# Carduino.net
KiCad netlist of a schematic drawn in Altium Designer
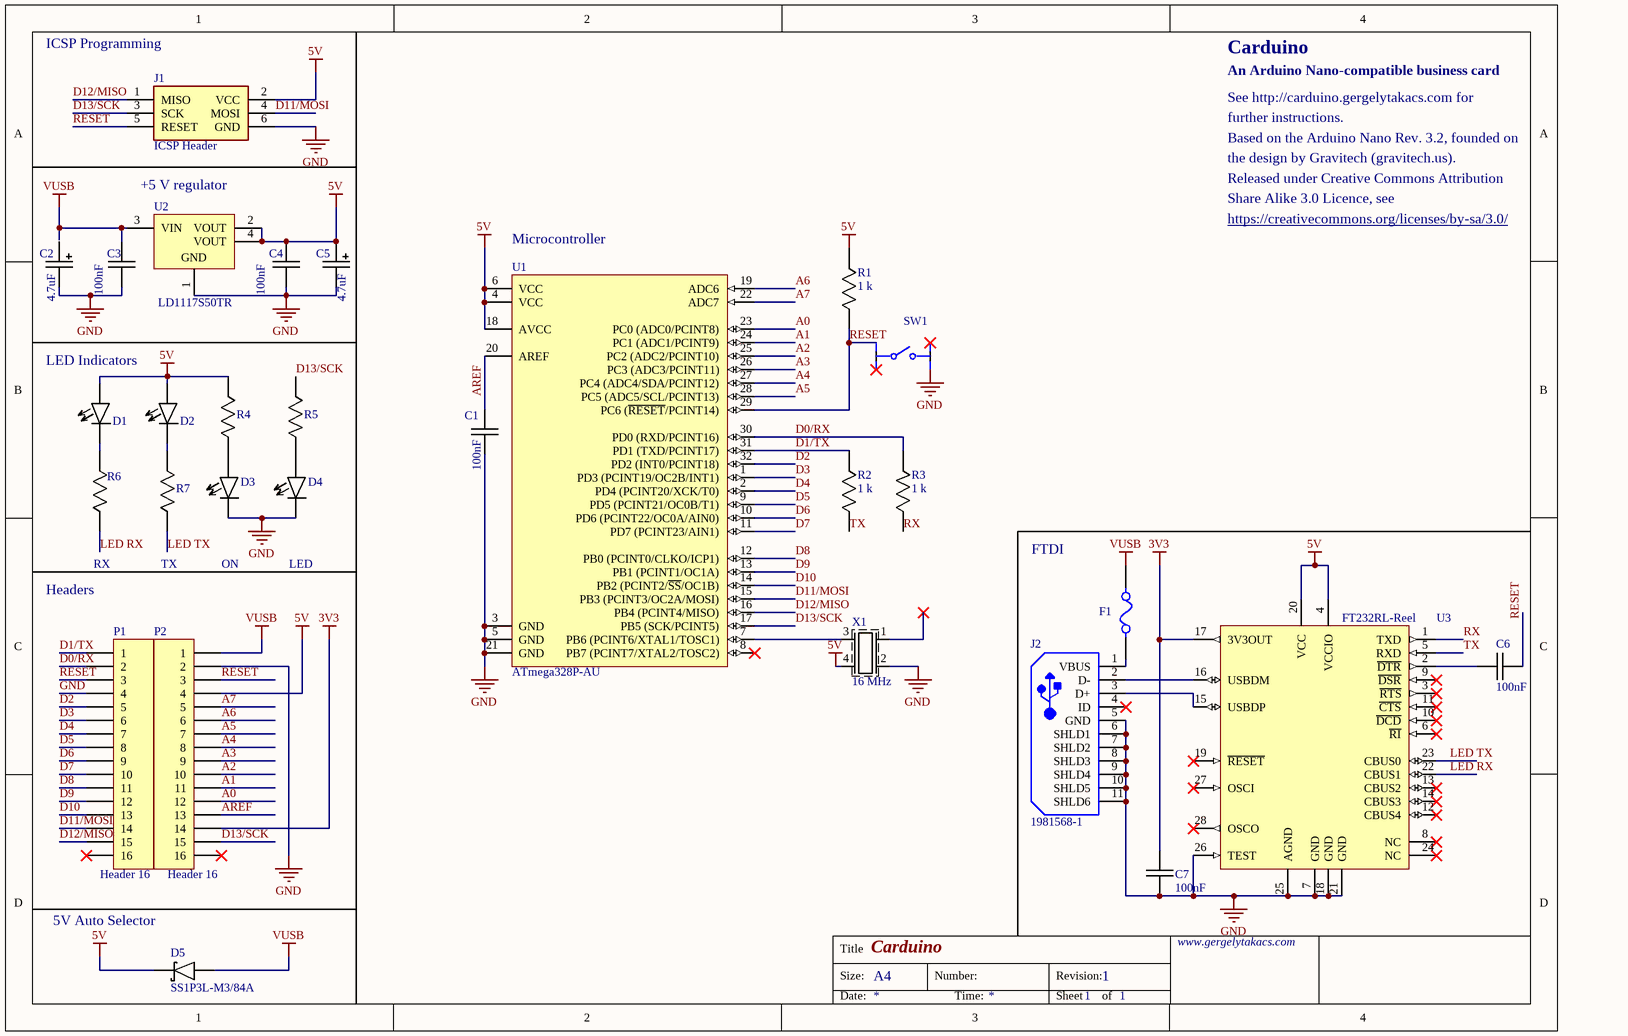
[diagram p0: Carduino.SchDoc]

(export (version "E")
  (design (tool "Eeschema 10.0.6"))
  (components
    (comp (ref "C1")
      (value "100nF")
      (footprint "CAPC2013X09N")
      (description "Ceramic condenser MLCC; 100nF; 25V; X7R; ±10%; SMD; 0805")
      (libsource (lib "Capacitors") (part "100 uF,  ceramic, 0805, Kemet"))
    )
    (comp (ref "C2")
      (value "4.7uF")
      (footprint "CAP body B")
      (description "4,7uF; 25VDC; SMD; Puzd: B; ±10%; -55÷125°C")
      (libsource (lib "Capacitors") (part "4.7uF, Tantallum"))
    )
    (comp (ref "C3")
      (value "100nF")
      (footprint "CAPC2013X09N")
      (description "Ceramic condenser MLCC; 100nF; 25V; X7R; ±10%; SMD; 0805")
      (libsource (lib "Capacitors") (part "100 uF,  ceramic, 0805, Kemet"))
    )
    (comp (ref "C4")
      (value "100nF")
      (footprint "CAPC2013X09N")
      (description "Ceramic condenser MLCC; 100nF; 25V; X7R; ±10%; SMD; 0805")
      (libsource (lib "Capacitors") (part "100 uF,  ceramic, 0805, Kemet"))
    )
    (comp (ref "C5")
      (value "4.7uF")
      (footprint "CAP body B")
      (description "4,7uF; 25VDC; SMD; Puzd: B; ±10%; -55÷125°C")
      (libsource (lib "Capacitors") (part "4.7uF, Tantallum"))
    )
    (comp (ref "C6")
      (value "100nF")
      (footprint "CAPC2013X09N")
      (description "Ceramic condenser MLCC; 100nF; 25V; X7R; ±10%; SMD; 0805")
      (libsource (lib "Capacitors") (part "100 uF,  ceramic, 0805, Kemet"))
    )
    (comp (ref "C7")
      (value "100nF")
      (footprint "CAPC2013X09N")
      (description "Ceramic condenser MLCC; 100nF; 25V; X7R; ±10%; SMD; 0805")
      (libsource (lib "Capacitors") (part "100 uF,  ceramic, 0805, Kemet"))
    )
    (comp (ref "D1")
      (value "OSXX0805C1E")
      (footprint "DIOC2012X09N")
      (description "OptoSupply Single Chip LED 0805")
      (fields
        (field (name "CREATOR") "Gergely Takacs")
        (field (name "CREATOR WWW") "http://www.gergelytakacs.com")
      )
      (libsource (lib "OptoSupplyLED") (part "OptoSupply RED"))
    )
    (comp (ref "D2")
      (value "OSXX0805C1E")
      (footprint "DIOC2012X09N")
      (description "OptoSupply Single Chip LED 0805")
      (fields
        (field (name "CREATOR") "Gergely Takacs")
        (field (name "CREATOR WWW") "http://www.gergelytakacs.com")
      )
      (libsource (lib "OptoSupplyLED") (part "OptoSupply RED"))
    )
    (comp (ref "D3")
      (value "OSXX0805C1E")
      (footprint "DIOC2012X09N")
      (description "OptoSupply Single Chip LED 0805")
      (fields
        (field (name "CREATOR") "Gergely Takacs")
        (field (name "CREATOR WWW") "http://www.gergelytakacs.com")
      )
      (libsource (lib "OptoSupplyLED") (part "OptoSupply RED"))
    )
    (comp (ref "D4")
      (value "OSXX0805C1E")
      (footprint "DIOC2012X09N")
      (description "OptoSupply Single Chip LED 0805")
      (fields
        (field (name "CREATOR") "Gergely Takacs")
        (field (name "CREATOR WWW") "http://www.gergelytakacs.com")
      )
      (libsource (lib "OptoSupplyLED") (part "OptoSupply RED"))
    )
    (comp (ref "D5")
      (value "SS1P3L-M3/84A")
      (footprint "DIOM3420X11N")
      (description "VISHAY SS1P3L-M3/84A  Dióda: usmerňovacia Schottky; SMD; 30V; 1A; DO220AA, SMP")
      (libsource (lib "Diodes") (part "SS1P3L"))
    )
    (comp (ref "F1")
      (value "ECE SR050-06")
      (footprint "RESC2113X12N")
      (description "FUSE PTC RESETTABLE .50A")
      (libsource (lib "Fuses") (part "ECE SR050-06"))
    )
    (comp (ref "J1")
      (value "Conn_3M_961206-6404-AR_eec")
      (footprint "3M_961206-6404-AR_0")
      (description "CONN HEADER VERT DUAL 6POS GOLD")
      (fields
        (field (name "MANUFACTURER") "3M")
        (field (name "MOUSER PART NUMBER") "517-9612066404AR")
        (field (name "PART NUMBER") "ICSP Header")
      )
      (libsource (lib "ICSP") (part "Conn_3M_961206-6404-AR_eec"))
    )
    (comp (ref "J2")
      (value "1981568-1")
      (footprint "TECO-1981568-5_V")
      (description "Micro USB Receptacle Standard Type B Assy, 5-Pin SMD, RoHS, Tape and Reel")
      (fields (field (name "MANUFACTURER") "TE Connectivity"))
      (libsource (lib "Connectors") (part "1981568-1"))
    )
    (comp (ref "P1")
      (value "Header 16")
      (footprint "HDR1X16")
      (description "Header, 16-Pin")
      (fields (field (name "PUBLISHER") "Altium Limited"))
      (libsource (lib "Miscellaneous Connectors") (part "Header 16"))
    )
    (comp (ref "P2")
      (value "Header 16")
      (footprint "HDR1X16")
      (description "Header, 16-Pin")
      (fields (field (name "PUBLISHER") "Altium Limited"))
      (libsource (lib "") (part "Header 16_1"))
    )
    (comp (ref "R1")
      (value "1 k")
      (footprint "RESC2112X05N")
      (description "ROYAL OHM HP05W3F1001T5E  Rezistor: thick film; vysokovýkonný; SMD; 0805; 1kΩ; 0,3W; ±1%")
      (libsource (lib "Resistors") (part "1k, 0805, Royal Ohm"))
    )
    (comp (ref "R2")
      (value "1 k")
      (footprint "RESC2112X05N")
      (description "ROYAL OHM HP05W3F1001T5E  Rezistor: thick film; vysokovýkonný; SMD; 0805; 1kΩ; 0,3W; ±1%")
      (libsource (lib "Resistors") (part "1k, 0805, Royal Ohm"))
    )
    (comp (ref "R3")
      (value "1 k")
      (footprint "RESC2112X05N")
      (description "ROYAL OHM HP05W3F1001T5E  Rezistor: thick film; vysokovýkonný; SMD; 0805; 1kΩ; 0,3W; ±1%")
      (libsource (lib "Resistors") (part "1k, 0805, Royal Ohm"))
    )
    (comp (ref "R4")
      (value "270 Ohm, 0805")
      (footprint "RESC2112X05N")
      (description "VISHAY CRCW...BC Thick Film Commodity Resistor")
      (libsource (lib "Vishay Resistors") (part "270 Ohm, 0805, Resistor"))
    )
    (comp (ref "R5")
      (value "270 Ohm, 0805")
      (footprint "RESC2112X05N")
      (description "VISHAY CRCW...BC Thick Film Commodity Resistor")
      (libsource (lib "Vishay Resistors") (part "270 Ohm, 0805, Resistor"))
    )
    (comp (ref "R6")
      (value "270 Ohm, 0805")
      (footprint "RESC2112X05N")
      (description "VISHAY CRCW...BC Thick Film Commodity Resistor")
      (libsource (lib "Vishay Resistors") (part "270 Ohm, 0805, Resistor"))
    )
    (comp (ref "R7")
      (value "270 Ohm, 0805")
      (footprint "RESC2112X05N")
      (description "VISHAY CRCW...BC Thick Film Commodity Resistor")
      (libsource (lib "Vishay Resistors") (part "270 Ohm, 0805, Resistor"))
    )
    (comp (ref "SW1")
      (value "Switch_TE_1825910-7_eec")
      (footprint "TE_1825910-7_0")
      (description "SWITCH Tactile Switch SPST-NO Top Actuated Through Hole")
      (fields (field (name "PART NUMBER") "1825910-7") (field (name "MANUFACTURER") "TE"))
      (libsource (lib "Switches") (part "Switch_TE_1825910-7_eec"))
    )
    (comp (ref "U1")
      (value "ATmega328P-AU")
      (footprint "32A_N")
      (libsource (lib "Atmel Microcontroller megaAVR") (part "ATmega328P-AU"))
    )
    (comp (ref "U2")
      (value "LD1117S50TR")
      (footprint "SOT-223_N")
      (description "Fixed Low Drop Positive Voltage Regulator, 5V, 4-Pin SOT-223, Tape and Reel")
      (libsource (lib "STMicroelectronics Power Management Linear Regulator") (part "LD1117S50TR"))
    )
    (comp (ref "U3")
      (value "FT232RL-Reel")
      (footprint "SSOP-28_N")
      (description "USB UART Asynchronous Serial Data Transfer Chip, 28-pin SSOP, Tape and Reel")
      (fields (field (name "MANUFACTURER") "FTDI"))
      (libsource (lib "FTDI FT Series") (part "FT232RL-Reel"))
    )
    (comp (ref "X1")
      (value "16 MHz")
      (footprint "DFN598P720X140-4N")
      (description "QD FREQUENCY PRODUCTS LF SPXO018034")
      (libsource (lib "Xtals") (part "16 MHz, IQD FREQUENCY PRODUCTS"))
    )
  )
  (nets
    (net (code "1") (name "/A0") (class "Default")
      (node (ref "P2") (pin "12") (pinfunction "12_12") (pintype "passive"))
      (node (ref "U1") (pin "23") (pinfunction "PC0_(ADC0/PCINT8)_23") (pintype "bidirectional"))
    )
    (net (code "2") (name "/A1") (class "Default")
      (node (ref "P2") (pin "11") (pinfunction "11_11") (pintype "passive"))
      (node (ref "U1") (pin "24") (pinfunction "PC1_(ADC1/PCINT9)_24") (pintype "bidirectional"))
    )
    (net (code "3") (name "/A2") (class "Default")
      (node (ref "P2") (pin "10") (pinfunction "10_10") (pintype "passive"))
      (node (ref "U1") (pin "25") (pinfunction "PC2_(ADC2/PCINT10)_25") (pintype "bidirectional"))
    )
    (net (code "4") (name "/A3") (class "Default")
      (node (ref "P2") (pin "9") (pinfunction "9_9") (pintype "passive"))
      (node (ref "U1") (pin "26") (pinfunction "PC3_(ADC3/PCINT11)_26") (pintype "bidirectional"))
    )
    (net (code "5") (name "/A4") (class "Default")
      (node (ref "P2") (pin "8") (pinfunction "8_8") (pintype "passive"))
      (node (ref "U1") (pin "27") (pinfunction "PC4_(ADC4/SDA/PCINT12)_27") (pintype "bidirectional"))
    )
    (net (code "6") (name "/A5") (class "Default")
      (node (ref "P2") (pin "7") (pinfunction "7_7") (pintype "passive"))
      (node (ref "U1") (pin "28") (pinfunction "PC5_(ADC5/SCL/PCINT13)_28") (pintype "bidirectional"))
    )
    (net (code "7") (name "/A6") (class "Default")
      (node (ref "P2") (pin "6") (pinfunction "6_6") (pintype "passive"))
      (node (ref "U1") (pin "19") (pinfunction "ADC6_19") (pintype "input"))
    )
    (net (code "8") (name "/A7") (class "Default")
      (node (ref "P2") (pin "5") (pinfunction "5_5") (pintype "passive"))
      (node (ref "U1") (pin "22") (pinfunction "ADC7_22") (pintype "input"))
    )
    (net (code "9") (name "/AREF") (class "Default")
      (node (ref "C1") (pin "1") (pinfunction "1_1") (pintype "passive"))
      (node (ref "P2") (pin "13") (pinfunction "13_13") (pintype "passive"))
      (node (ref "U1") (pin "20") (pinfunction "AREF_20") (pintype "passive"))
    )
    (net (code "10") (name "/D0{slash}RX") (class "Default")
      (node (ref "P1") (pin "2") (pinfunction "2_2") (pintype "passive"))
      (node (ref "R3") (pin "2") (pinfunction "2_2") (pintype "passive"))
      (node (ref "U1") (pin "30") (pinfunction "PD0_(RXD/PCINT16)_30") (pintype "bidirectional"))
    )
    (net (code "11") (name "/D1{slash}TX") (class "Default")
      (node (ref "P1") (pin "1") (pinfunction "1_1") (pintype "passive"))
      (node (ref "R2") (pin "1") (pinfunction "1_1") (pintype "passive"))
      (node (ref "U1") (pin "31") (pinfunction "PD1_(TXD/PCINT17)_31") (pintype "bidirectional"))
    )
    (net (code "12") (name "/D2") (class "Default")
      (node (ref "P1") (pin "5") (pinfunction "5_5") (pintype "passive"))
      (node (ref "U1") (pin "32") (pinfunction "PD2_(INT0/PCINT18)_32") (pintype "bidirectional"))
    )
    (net (code "13") (name "/D3") (class "Default")
      (node (ref "P1") (pin "6") (pinfunction "6_6") (pintype "passive"))
      (node (ref "U1") (pin "1") (pinfunction "PD3_(PCINT19/OC2B/INT1)_1") (pintype "bidirectional"))
    )
    (net (code "14") (name "/D4") (class "Default")
      (node (ref "P1") (pin "7") (pinfunction "7_7") (pintype "passive"))
      (node (ref "U1") (pin "2") (pinfunction "PD4_(PCINT20/XCK/T0)_2") (pintype "bidirectional"))
    )
    (net (code "15") (name "/D5") (class "Default")
      (node (ref "P1") (pin "8") (pinfunction "8_8") (pintype "passive"))
      (node (ref "U1") (pin "9") (pinfunction "PD5_(PCINT21/OC0B/T1)_9") (pintype "bidirectional"))
    )
    (net (code "16") (name "/D6") (class "Default")
      (node (ref "P1") (pin "9") (pinfunction "9_9") (pintype "passive"))
      (node (ref "U1") (pin "10") (pinfunction "PD6_(PCINT22/OC0A/AIN0)_10") (pintype "bidirectional"))
    )
    (net (code "17") (name "/D7") (class "Default")
      (node (ref "P1") (pin "10") (pinfunction "10_10") (pintype "passive"))
      (node (ref "U1") (pin "11") (pinfunction "PD7_(PCINT23/AIN1)_11") (pintype "bidirectional"))
    )
    (net (code "18") (name "/D8") (class "Default")
      (node (ref "P1") (pin "11") (pinfunction "11_11") (pintype "passive"))
      (node (ref "U1") (pin "12") (pinfunction "PB0_(PCINT0/CLKO/ICP1)_12") (pintype "bidirectional"))
    )
    (net (code "19") (name "/D9") (class "Default")
      (node (ref "P1") (pin "12") (pinfunction "12_12") (pintype "passive"))
      (node (ref "U1") (pin "13") (pinfunction "PB1_(PCINT1/OC1A)_13") (pintype "bidirectional"))
    )
    (net (code "20") (name "/D10") (class "Default")
      (node (ref "P1") (pin "13") (pinfunction "13_13") (pintype "passive"))
      (node (ref "U1") (pin "14") (pinfunction "PB2_(PCINT2/~{SS}/OC1B)_14") (pintype "bidirectional"))
    )
    (net (code "21") (name "/D11{slash}MOSI") (class "Default")
      (node (ref "J1") (pin "4") (pinfunction "MOSI_4") (pintype "passive"))
      (node (ref "P1") (pin "14") (pinfunction "14_14") (pintype "passive"))
      (node (ref "U1") (pin "15") (pinfunction "PB3_(PCINT3/OC2A/MOSI)_15") (pintype "bidirectional"))
    )
    (net (code "22") (name "/D12{slash}MISO") (class "Default")
      (node (ref "J1") (pin "1") (pinfunction "MISO_1") (pintype "passive"))
      (node (ref "P1") (pin "15") (pinfunction "15_15") (pintype "passive"))
      (node (ref "U1") (pin "16") (pinfunction "PB4_(PCINT4/MISO)_16") (pintype "bidirectional"))
    )
    (net (code "23") (name "/D13{slash}SCK") (class "Default")
      (node (ref "J1") (pin "3") (pinfunction "SCK_3") (pintype "passive"))
      (node (ref "P2") (pin "15") (pinfunction "15_15") (pintype "passive"))
      (node (ref "R5") (pin "1") (pinfunction "1_1") (pintype "passive"))
      (node (ref "U1") (pin "17") (pinfunction "PB5_(SCK/PCINT5)_17") (pintype "bidirectional"))
    )
    (net (code "24") (name "/LED RX") (class "Default")
      (node (ref "R6") (pin "2") (pinfunction "2_2") (pintype "passive"))
      (node (ref "U3") (pin "22") (pinfunction "CBUS1_22") (pintype "bidirectional"))
    )
    (net (code "25") (name "/LED TX") (class "Default")
      (node (ref "R7") (pin "2") (pinfunction "2_2") (pintype "passive"))
      (node (ref "U3") (pin "23") (pinfunction "CBUS0_23") (pintype "bidirectional"))
    )
    (net (code "26") (name "/RESET") (class "Default")
      (node (ref "C6") (pin "2") (pinfunction "2_2") (pintype "passive"))
      (node (ref "J1") (pin "5") (pinfunction "RESET_5") (pintype "passive"))
      (node (ref "P1") (pin "3") (pinfunction "3_3") (pintype "passive"))
      (node (ref "P2") (pin "3") (pinfunction "3_3") (pintype "passive"))
      (node (ref "R1") (pin "2") (pinfunction "2_2") (pintype "passive"))
      (node (ref "SW1") (pin "1") (pinfunction "1_1") (pintype "passive"))
      (node (ref "U1") (pin "29") (pinfunction "PC6_(~{RESET}/PCINT14)_29") (pintype "bidirectional"))
    )
    (net (code "27") (name "/RX") (class "Default")
      (node (ref "R3") (pin "1") (pinfunction "1_1") (pintype "passive"))
      (node (ref "U3") (pin "1") (pinfunction "TXD_1") (pintype "output"))
    )
    (net (code "28") (name "/TX") (class "Default")
      (node (ref "R2") (pin "2") (pinfunction "2_2") (pintype "passive"))
      (node (ref "U3") (pin "5") (pinfunction "RXD_5") (pintype "input"))
    )
    (net (code "29") (name "3V3") (class "Default")
      (node (ref "C7") (pin "2") (pinfunction "2_2") (pintype "passive"))
      (node (ref "P2") (pin "14") (pinfunction "14_14") (pintype "passive"))
      (node (ref "U3") (pin "17") (pinfunction "3V3OUT_17") (pintype "output"))
    )
    (net (code "30") (name "5V") (class "Default")
      (node (ref "C4") (pin "1") (pinfunction "1_1") (pintype "passive"))
      (node (ref "C5") (pin "1") (pinfunction "1_1") (pintype "passive"))
      (node (ref "D1") (pin "2") (pinfunction "2_2") (pintype "passive"))
      (node (ref "D2") (pin "2") (pinfunction "2_2") (pintype "passive"))
      (node (ref "D5") (pin "1") (pinfunction "1_1") (pintype "passive"))
      (node (ref "J1") (pin "2") (pinfunction "VCC_2") (pintype "passive"))
      (node (ref "P2") (pin "4") (pinfunction "4_4") (pintype "passive"))
      (node (ref "R1") (pin "1") (pinfunction "1_1") (pintype "passive"))
      (node (ref "R4") (pin "1") (pinfunction "1_1") (pintype "passive"))
      (node (ref "U1") (pin "18") (pinfunction "AVCC_18") (pintype "power_in"))
      (node (ref "U1") (pin "4") (pinfunction "VCC_4") (pintype "power_in"))
      (node (ref "U1") (pin "6") (pinfunction "VCC_6") (pintype "power_in"))
      (node (ref "U2") (pin "2") (pinfunction "VOUT_2") (pintype "power_in"))
      (node (ref "U2") (pin "4") (pinfunction "VOUT_4") (pintype "power_in"))
      (node (ref "U3") (pin "20") (pinfunction "VCC_20") (pintype "power_in"))
      (node (ref "U3") (pin "4") (pinfunction "VCCIO_4") (pintype "power_in"))
      (node (ref "X1") (pin "4") (pinfunction "4_4") (pintype "passive"))
    )
    (net (code "31") (name "GND") (class "Default")
      (node (ref "C1") (pin "2") (pinfunction "2_2") (pintype "passive"))
      (node (ref "C2") (pin "2") (pinfunction "2_2") (pintype "passive"))
      (node (ref "C3") (pin "1") (pinfunction "1_1") (pintype "passive"))
      (node (ref "C4") (pin "2") (pinfunction "2_2") (pintype "passive"))
      (node (ref "C5") (pin "2") (pinfunction "2_2") (pintype "passive"))
      (node (ref "C7") (pin "1") (pinfunction "1_1") (pintype "passive"))
      (node (ref "D3") (pin "1") (pinfunction "1_1") (pintype "passive"))
      (node (ref "D4") (pin "1") (pinfunction "1_1") (pintype "passive"))
      (node (ref "J1") (pin "6") (pinfunction "GND_6") (pintype "passive"))
      (node (ref "J2") (pin "10") (pinfunction "SHLD5_10") (pintype "passive"))
      (node (ref "J2") (pin "11") (pinfunction "SHLD6_11") (pintype "passive"))
      (node (ref "J2") (pin "5") (pinfunction "GND_5") (pintype "passive"))
      (node (ref "J2") (pin "6") (pinfunction "SHLD1_6") (pintype "passive"))
      (node (ref "J2") (pin "7") (pinfunction "SHLD2_7") (pintype "passive"))
      (node (ref "J2") (pin "8") (pinfunction "SHLD3_8") (pintype "passive"))
      (node (ref "J2") (pin "9") (pinfunction "SHLD4_9") (pintype "passive"))
      (node (ref "P1") (pin "4") (pinfunction "4_4") (pintype "passive"))
      (node (ref "P2") (pin "2") (pinfunction "2_2") (pintype "passive"))
      (node (ref "SW1") (pin "4") (pinfunction "4_4") (pintype "passive"))
      (node (ref "U1") (pin "21") (pinfunction "GND_21") (pintype "power_in"))
      (node (ref "U1") (pin "3") (pinfunction "GND_3") (pintype "power_in"))
      (node (ref "U1") (pin "5") (pinfunction "GND_5") (pintype "power_in"))
      (node (ref "U2") (pin "1") (pinfunction "GND_1") (pintype "power_in"))
      (node (ref "U3") (pin "18") (pinfunction "GND_18") (pintype "power_in"))
      (node (ref "U3") (pin "21") (pinfunction "GND_21") (pintype "power_in"))
      (node (ref "U3") (pin "25") (pinfunction "AGND_25") (pintype "power_in"))
      (node (ref "U3") (pin "26") (pinfunction "TEST_26") (pintype "input"))
      (node (ref "U3") (pin "7") (pinfunction "GND_7") (pintype "power_in"))
      (node (ref "X1") (pin "2") (pinfunction "2_2") (pintype "passive"))
    )
    (net (code "32") (name "Net-(D1-Pad1)") (class "Default")
      (node (ref "D1") (pin "1") (pinfunction "1_1") (pintype "passive"))
      (node (ref "R6") (pin "1") (pinfunction "1_1") (pintype "passive"))
    )
    (net (code "33") (name "Net-(D2-Pad1)") (class "Default")
      (node (ref "D2") (pin "1") (pinfunction "1_1") (pintype "passive"))
      (node (ref "R7") (pin "1") (pinfunction "1_1") (pintype "passive"))
    )
    (net (code "34") (name "Net-(D3-Pad2)") (class "Default")
      (node (ref "D3") (pin "2") (pinfunction "2_2") (pintype "passive"))
      (node (ref "R4") (pin "2") (pinfunction "2_2") (pintype "passive"))
    )
    (net (code "35") (name "Net-(D4-Pad2)") (class "Default")
      (node (ref "D4") (pin "2") (pinfunction "2_2") (pintype "passive"))
      (node (ref "R5") (pin "2") (pinfunction "2_2") (pintype "passive"))
    )
    (net (code "36") (name "Net-(J2-D+)") (class "Default")
      (node (ref "J2") (pin "3") (pinfunction "D+_3") (pintype "passive"))
      (node (ref "U3") (pin "15") (pinfunction "USBDP_15") (pintype "bidirectional"))
    )
    (net (code "37") (name "Net-(J2-D-)") (class "Default")
      (node (ref "J2") (pin "2") (pinfunction "D-_2") (pintype "passive"))
      (node (ref "U3") (pin "16") (pinfunction "USBDM_16") (pintype "bidirectional"))
    )
    (net (code "38") (name "Net-(J2-VBUS)") (class "Default")
      (node (ref "F1") (pin "1") (pinfunction "1_1") (pintype "passive"))
      (node (ref "J2") (pin "1") (pinfunction "VBUS_1") (pintype "passive"))
    )
    (net (code "39") (name "Net-(U1-PB6_(PCINT6{slash}XTAL1{slash}TOSC1))") (class "Default")
      (node (ref "U1") (pin "7") (pinfunction "PB6_(PCINT6/XTAL1/TOSC1)_7") (pintype "bidirectional"))
      (node (ref "X1") (pin "3") (pinfunction "3_3") (pintype "passive"))
    )
    (net (code "40") (name "Net-(U3-~{DTR})") (class "Default")
      (node (ref "C6") (pin "1") (pinfunction "1_1") (pintype "passive"))
      (node (ref "U3") (pin "2") (pinfunction "~{DTR}_2") (pintype "output"))
    )
    (net (code "41") (name "VUSB") (class "Default")
      (node (ref "C3") (pin "2") (pinfunction "2_2") (pintype "passive"))
      (node (ref "D5") (pin "2") (pinfunction "2_2") (pintype "passive"))
      (node (ref "F1") (pin "2") (pinfunction "2_2") (pintype "passive"))
      (node (ref "P2") (pin "1") (pinfunction "1_1") (pintype "passive"))
      (node (ref "U2") (pin "3") (pinfunction "VIN_3") (pintype "power_in"))
    )
    (net (code "42") (name "unconnected-(C2-Pad1)") (class "Default")
      (node (ref "C2") (pin "1") (pinfunction "1_1") (pintype "passive"))
    )
    (net (code "43") (name "unconnected-(J2-ID-Pad4)") (class "Default")
      (node (ref "J2") (pin "4") (pinfunction "ID_4") (pintype "passive+no_connect"))
    )
    (net (code "44") (name "unconnected-(P1-Pad16)") (class "Default")
      (node (ref "P1") (pin "16") (pinfunction "16_16") (pintype "passive+no_connect"))
    )
    (net (code "45") (name "unconnected-(P2-Pad16)") (class "Default")
      (node (ref "P2") (pin "16") (pinfunction "16_16") (pintype "passive+no_connect"))
    )
    (net (code "46") (name "unconnected-(SW1-Pad2)") (class "Default")
      (node (ref "SW1") (pin "2") (pinfunction "2_2") (pintype "passive+no_connect"))
    )
    (net (code "47") (name "unconnected-(SW1-Pad3)") (class "Default")
      (node (ref "SW1") (pin "3") (pinfunction "3_3") (pintype "passive+no_connect"))
    )
    (net (code "48") (name "unconnected-(U1-PB7_(PCINT7{slash}XTAL2{slash}TOSC2)-Pad8)") (class "Default")
      (node (ref "U1") (pin "8") (pinfunction "PB7_(PCINT7/XTAL2/TOSC2)_8") (pintype "bidirectional+no_connect"))
    )
    (net (code "49") (name "unconnected-(U3-CBUS2-Pad13)") (class "Default")
      (node (ref "U3") (pin "13") (pinfunction "CBUS2_13") (pintype "bidirectional+no_connect"))
    )
    (net (code "50") (name "unconnected-(U3-CBUS3-Pad14)") (class "Default")
      (node (ref "U3") (pin "14") (pinfunction "CBUS3_14") (pintype "bidirectional+no_connect"))
    )
    (net (code "51") (name "unconnected-(U3-CBUS4-Pad12)") (class "Default")
      (node (ref "U3") (pin "12") (pinfunction "CBUS4_12") (pintype "bidirectional+no_connect"))
    )
    (net (code "52") (name "unconnected-(U3-NC-Pad8)") (class "Default")
      (node (ref "U3") (pin "8") (pinfunction "NC_8") (pintype "passive+no_connect"))
    )
    (net (code "53") (name "unconnected-(U3-NC-Pad24)") (class "Default")
      (node (ref "U3") (pin "24") (pinfunction "NC_24") (pintype "passive+no_connect"))
    )
    (net (code "54") (name "unconnected-(U3-OSCI-Pad27)") (class "Default")
      (node (ref "U3") (pin "27") (pinfunction "OSCI_27") (pintype "input+no_connect"))
    )
    (net (code "55") (name "unconnected-(U3-OSCO-Pad28)") (class "Default")
      (node (ref "U3") (pin "28") (pinfunction "OSCO_28") (pintype "output+no_connect"))
    )
    (net (code "56") (name "unconnected-(U3-~{CTS}-Pad11)") (class "Default")
      (node (ref "U3") (pin "11") (pinfunction "~{CTS}_11") (pintype "input+no_connect"))
    )
    (net (code "57") (name "unconnected-(U3-~{DCD}-Pad10)") (class "Default")
      (node (ref "U3") (pin "10") (pinfunction "~{DCD}_10") (pintype "input+no_connect"))
    )
    (net (code "58") (name "unconnected-(U3-~{DSR}-Pad9)") (class "Default")
      (node (ref "U3") (pin "9") (pinfunction "~{DSR}_9") (pintype "input+no_connect"))
    )
    (net (code "59") (name "unconnected-(U3-~{RESET}-Pad19)") (class "Default")
      (node (ref "U3") (pin "19") (pinfunction "~{RESET}_19") (pintype "input+no_connect"))
    )
    (net (code "60") (name "unconnected-(U3-~{RI}-Pad6)") (class "Default")
      (node (ref "U3") (pin "6") (pinfunction "~{RI}_6") (pintype "input+no_connect"))
    )
    (net (code "61") (name "unconnected-(U3-~{RTS}-Pad3)") (class "Default")
      (node (ref "U3") (pin "3") (pinfunction "~{RTS}_3") (pintype "output+no_connect"))
    )
    (net (code "62") (name "unconnected-(X1-Pad1)") (class "Default")
      (node (ref "X1") (pin "1") (pinfunction "1_1") (pintype "passive+no_connect"))
    )
  )
)
